# drv8886_breakout.net
KiCad netlist of a schematic drawn in Altium Designer
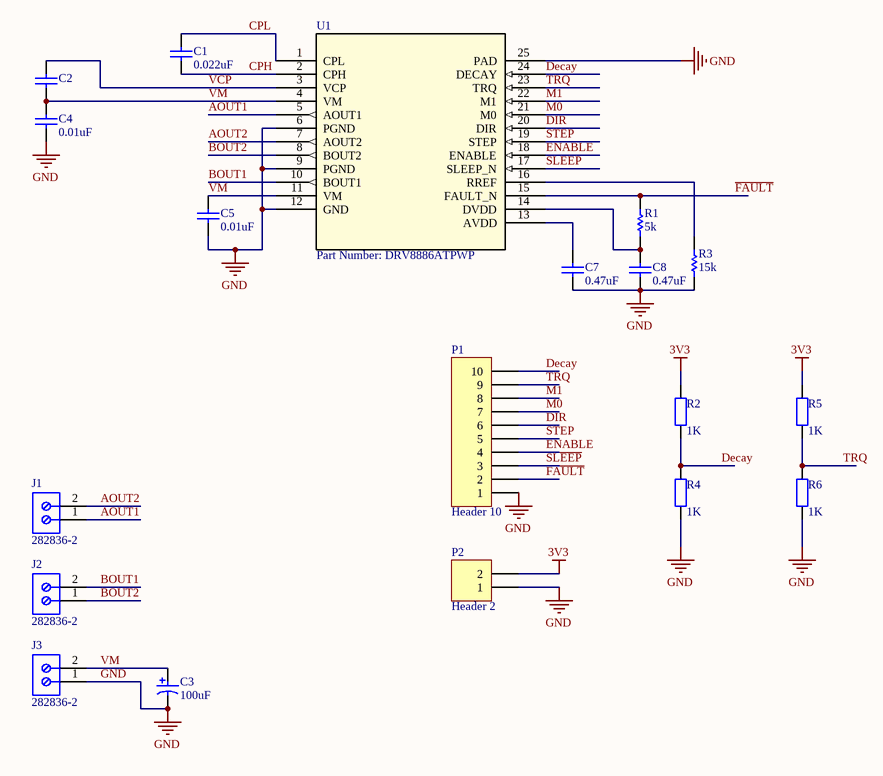
[diagram p0: drv8886_breakout.SchDoc]

(export (version "E")
  (design (tool "Eeschema 10.0.6"))
  (components
    (comp (ref "C1")
      (value "0.022uF")
      (footprint "CAPC1608X87X35ML15T15")
      (fields (field (name "PART NUMBER") "C0603C223K4RACTU") (field (name "MANUFACTURER") "Kemet"))
      (libsource (lib "Altium Content Vault") (part "CAP"))
    )
    (comp (ref "C2")
      (value "0.22uF")
      (footprint "TDK-C1608-2_A_M")
      (description "Cap Ceramic, 0.22 uF, +/- 10%, -55 to 125 degC, 2-Pin SMD (0603), RoHS, Tape and Reel")
      (fields (field (name "MANUFACTURER") "TDK") (field (name "TOLERANCE") "±10%"))
      (libsource (lib "Altium Content Vault") (part "CAP-NP-2"))
    )
    (comp (ref "C3")
      (value "100uF")
      (footprint "PNSC-FK-V-F_V")
      (fields (field (name "MANUFACTURER") "Panasonic"))
      (libsource (lib "Altium Content Vault") (part "CAP-P-2"))
    )
    (comp (ref "C4")
      (value "0.01uF")
      (footprint "CAPC1608X87X35LL15T15")
      (fields (field (name "MANUFACTURER") "Kemet") (field (name "PART NUMBER") "C0603X103K5RACTU"))
      (libsource (lib "Altium Content Vault") (part "CAP"))
    )
    (comp (ref "C5")
      (value "0.01uF")
      (footprint "CAPC1608X87X35LL15T15")
      (fields (field (name "MANUFACTURER") "Kemet") (field (name "PART NUMBER") "C0603X103K5RACTU"))
      (libsource (lib "Altium Content Vault") (part "CAP"))
    )
    (comp (ref "C7")
      (value "0.47uF")
      (footprint "CAPC1608X90X35ML15T15")
      (fields
        (field (name "PART NUMBER") "06033C474KAT2A")
        (field (name "MANUFACTURER") "AVX Interconnect / Elco")
      )
      (libsource (lib "Altium Content Vault") (part "CAP"))
    )
    (comp (ref "C8")
      (value "0.47uF")
      (footprint "CAPC1608X90X35ML15T15")
      (fields
        (field (name "PART NUMBER") "06033C474KAT2A")
        (field (name "MANUFACTURER") "AVX Interconnect / Elco")
      )
      (libsource (lib "Altium Content Vault") (part "CAP"))
    )
    (comp (ref "J1")
      (value "282836-2")
      (footprint "TECO-282836-2_V")
      (description "Female Header, Pitch 5 mm, 1 x 2 Position, Height 10 mm, Tail Length 3.5 mm, Rohs, Bulk")
      (fields (field (name "VOLTAGE") "300V") (field (name "MANUFACTURER") "TE Connectivity"))
      (libsource (lib "Altium Content Vault") (part "CN-1P-F-TB2"))
    )
    (comp (ref "J2")
      (value "282836-2")
      (footprint "TECO-282836-2_V")
      (description "Female Header, Pitch 5 mm, 1 x 2 Position, Height 10 mm, Tail Length 3.5 mm, Rohs, Bulk")
      (fields (field (name "VOLTAGE") "300V") (field (name "MANUFACTURER") "TE Connectivity"))
      (libsource (lib "Altium Content Vault") (part "CN-1P-F-TB2"))
    )
    (comp (ref "J3")
      (value "282836-2")
      (footprint "TECO-282836-2_V")
      (description "Female Header, Pitch 5 mm, 1 x 2 Position, Height 10 mm, Tail Length 3.5 mm, Rohs, Bulk")
      (fields (field (name "VOLTAGE") "300V") (field (name "MANUFACTURER") "TE Connectivity"))
      (libsource (lib "Altium Content Vault") (part "CN-1P-F-TB2"))
    )
    (comp (ref "P1")
      (value "Header 10")
      (footprint "HDR1X10")
      (description "Header, 10-Pin")
      (fields (field (name "PUBLISHER") "Altium Limited"))
      (libsource (lib "Miscellaneous Connectors") (part "Header 10"))
    )
    (comp (ref "P2")
      (value "Header 2")
      (footprint "HDR1X2")
      (description "Header, 2-Pin")
      (fields (field (name "PUBLISHER") "Altium Limited"))
      (libsource (lib "Miscellaneous Connectors") (part "Header 2"))
    )
    (comp (ref "R1")
      (value "5k")
      (footprint "RESC1608X55X25ML10T15")
      (description "Chip Resistor, 0 Ohm, +/- 5%, 0.1 W, -55 to 155 degC, 0603 (1608 Metric), RoHS, Tape and Reel")
      (fields (field (name "TOLERANCE") "5%") (field (name "MANUFACTURER") "Yageo"))
      (libsource (lib "Altium Content Vault") (part "RES-2"))
    )
    (comp (ref "R2")
      (value "1K")
      (footprint "AXIAL-0.4")
      (description "Resistor")
      (fields (field (name "Comment") "?") (field (name "PUBLISHER") "Altium Limited"))
      (libsource (lib "Miscellaneous Devices") (part "Res2"))
    )
    (comp (ref "R3")
      (value "15k")
      (footprint "RESC1608X55X25ML10T15")
      (description "Chip Resistor, 0 Ohm, +/- 5%, 0.1 W, -55 to 155 degC, 0603 (1608 Metric), RoHS, Tape and Reel")
      (fields (field (name "TOLERANCE") "5%") (field (name "MANUFACTURER") "Yageo"))
      (libsource (lib "Altium Content Vault") (part "RES-2"))
    )
    (comp (ref "R4")
      (value "1K")
      (footprint "AXIAL-0.4")
      (description "Resistor")
      (fields (field (name "Comment") "Res2") (field (name "PUBLISHER") "Altium Limited"))
      (libsource (lib "Miscellaneous Devices") (part "Res2"))
    )
    (comp (ref "R5")
      (value "1K")
      (footprint "AXIAL-0.4")
      (description "Resistor")
      (fields (field (name "Comment") "?") (field (name "PUBLISHER") "Altium Limited"))
      (libsource (lib "Miscellaneous Devices") (part "Res2"))
    )
    (comp (ref "R6")
      (value "1K")
      (footprint "AXIAL-0.4")
      (description "Resistor")
      (fields (field (name "Comment") "Res2") (field (name "PUBLISHER") "Altium Limited"))
      (libsource (lib "Miscellaneous Devices") (part "Res2"))
    )
    (comp (ref "U1")
      (value "Part Number: DRV8886ATPWP")
      (footprint "PWP0024B_N")
      (description "No Description Available")
      (fields
        (field (name "MANUFACTURER_PART_NUMBER") "DRV8886ATPWP")
        (field (name "COPYRIGHT") "Copyright (C) 2018 Accelerated Designs. All rights reserved")
      )
      (libsource (lib "2019-10-07_21-03-12") (part "DRV8886ATPWP"))
    )
  )
  (nets
    (net (code "1") (name "/AOUT1") (class "Default")
      (node (ref "J1") (pin "1") (pinfunction "1_1") (pintype "passive"))
      (node (ref "U1") (pin "5") (pinfunction "AOUT1_5") (pintype "output"))
    )
    (net (code "2") (name "/AOUT2") (class "Default")
      (node (ref "J1") (pin "2") (pinfunction "2_2") (pintype "passive"))
      (node (ref "U1") (pin "7") (pinfunction "AOUT2_7") (pintype "output"))
    )
    (net (code "3") (name "/BOUT1") (class "Default")
      (node (ref "J2") (pin "2") (pinfunction "2_2") (pintype "passive"))
      (node (ref "U1") (pin "10") (pinfunction "BOUT1_10") (pintype "output"))
    )
    (net (code "4") (name "/BOUT2") (class "Default")
      (node (ref "J2") (pin "1") (pinfunction "1_1") (pintype "passive"))
      (node (ref "U1") (pin "8") (pinfunction "BOUT2_8") (pintype "output"))
    )
    (net (code "5") (name "/CPH") (class "Default")
      (node (ref "C1") (pin "1") (pinfunction "1_1") (pintype "passive"))
      (node (ref "U1") (pin "2") (pinfunction "CPH_2") (pintype "passive"))
    )
    (net (code "6") (name "/CPL") (class "Default")
      (node (ref "C1") (pin "2") (pinfunction "2_2") (pintype "passive"))
      (node (ref "U1") (pin "1") (pinfunction "CPL_1") (pintype "passive"))
    )
    (net (code "7") (name "/DIR") (class "Default")
      (node (ref "P1") (pin "6") (pinfunction "6_6") (pintype "passive"))
      (node (ref "U1") (pin "20") (pinfunction "DIR_20") (pintype "input"))
    )
    (net (code "8") (name "/Decay") (class "Default")
      (node (ref "P1") (pin "10") (pinfunction "10_10") (pintype "passive"))
      (node (ref "R2") (pin "1") (pinfunction "1_1") (pintype "passive"))
      (node (ref "R4") (pin "2") (pinfunction "2_2") (pintype "passive"))
      (node (ref "U1") (pin "24") (pinfunction "DECAY_24") (pintype "input"))
    )
    (net (code "9") (name "/ENABLE") (class "Default")
      (node (ref "P1") (pin "4") (pinfunction "4_4") (pintype "passive"))
      (node (ref "U1") (pin "18") (pinfunction "ENABLE_18") (pintype "input"))
    )
    (net (code "10") (name "/FAULT") (class "Default")
      (node (ref "P1") (pin "2") (pinfunction "2_2") (pintype "passive"))
      (node (ref "R1") (pin "2") (pinfunction "2_2") (pintype "passive"))
      (node (ref "U1") (pin "15") (pinfunction "FAULT_N_15") (pintype "open_collector"))
    )
    (net (code "11") (name "/M0") (class "Default")
      (node (ref "P1") (pin "7") (pinfunction "7_7") (pintype "passive"))
      (node (ref "U1") (pin "21") (pinfunction "M0_21") (pintype "input"))
    )
    (net (code "12") (name "/M1") (class "Default")
      (node (ref "P1") (pin "8") (pinfunction "8_8") (pintype "passive"))
      (node (ref "U1") (pin "22") (pinfunction "M1_22") (pintype "input"))
    )
    (net (code "13") (name "/SLEEP") (class "Default")
      (node (ref "P1") (pin "3") (pinfunction "3_3") (pintype "passive"))
      (node (ref "U1") (pin "17") (pinfunction "SLEEP_N_17") (pintype "input"))
    )
    (net (code "14") (name "/STEP") (class "Default")
      (node (ref "P1") (pin "5") (pinfunction "5_5") (pintype "passive"))
      (node (ref "U1") (pin "19") (pinfunction "STEP_19") (pintype "input"))
    )
    (net (code "15") (name "/TRQ") (class "Default")
      (node (ref "P1") (pin "9") (pinfunction "9_9") (pintype "passive"))
      (node (ref "R5") (pin "1") (pinfunction "1_1") (pintype "passive"))
      (node (ref "R6") (pin "2") (pinfunction "2_2") (pintype "passive"))
      (node (ref "U1") (pin "23") (pinfunction "TRQ_23") (pintype "input"))
    )
    (net (code "16") (name "/VCP") (class "Default")
      (node (ref "C2") (pin "2") (pinfunction "2_2") (pintype "passive"))
      (node (ref "U1") (pin "3") (pinfunction "VCP_3") (pintype "passive"))
    )
    (net (code "17") (name "/VM") (class "Default")
      (node (ref "C2") (pin "1") (pinfunction "1_1") (pintype "passive"))
      (node (ref "C3") (pin "1") (pinfunction "1_1") (pintype "passive"))
      (node (ref "C4") (pin "1") (pinfunction "1_1") (pintype "passive"))
      (node (ref "C5") (pin "1") (pinfunction "1_1") (pintype "passive"))
      (node (ref "J3") (pin "2") (pinfunction "2_2") (pintype "passive"))
      (node (ref "U1") (pin "11") (pinfunction "VM_11") (pintype "power_in"))
      (node (ref "U1") (pin "4") (pinfunction "VM_4") (pintype "power_in"))
    )
    (net (code "18") (name "3V3") (class "Default")
      (node (ref "P2") (pin "2") (pinfunction "2_2") (pintype "passive"))
      (node (ref "R2") (pin "2") (pinfunction "2_2") (pintype "passive"))
      (node (ref "R5") (pin "2") (pinfunction "2_2") (pintype "passive"))
    )
    (net (code "19") (name "GND") (class "Default")
      (node (ref "C3") (pin "2") (pinfunction "2_2") (pintype "passive"))
      (node (ref "C4") (pin "2") (pinfunction "2_2") (pintype "passive"))
      (node (ref "C5") (pin "2") (pinfunction "2_2") (pintype "passive"))
      (node (ref "C7") (pin "1") (pinfunction "1_1") (pintype "passive"))
      (node (ref "C8") (pin "1") (pinfunction "1_1") (pintype "passive"))
      (node (ref "J3") (pin "1") (pinfunction "1_1") (pintype "passive"))
      (node (ref "P1") (pin "1") (pinfunction "1_1") (pintype "passive"))
      (node (ref "P2") (pin "1") (pinfunction "1_1") (pintype "passive"))
      (node (ref "R3") (pin "1") (pinfunction "1_1") (pintype "passive"))
      (node (ref "R4") (pin "1") (pinfunction "1_1") (pintype "passive"))
      (node (ref "R6") (pin "1") (pinfunction "1_1") (pintype "passive"))
      (node (ref "U1") (pin "12") (pinfunction "GND_12") (pintype "power_in"))
      (node (ref "U1") (pin "25") (pinfunction "PAD_25") (pintype "power_in"))
      (node (ref "U1") (pin "6") (pinfunction "PGND_6") (pintype "power_in"))
      (node (ref "U1") (pin "9") (pinfunction "PGND_9") (pintype "power_in"))
    )
    (net (code "20") (name "Net-(U1-AVDD)") (class "Default")
      (node (ref "C7") (pin "2") (pinfunction "2_2") (pintype "passive"))
      (node (ref "U1") (pin "13") (pinfunction "AVDD_13") (pintype "power_in"))
    )
    (net (code "21") (name "Net-(U1-DVDD)") (class "Default")
      (node (ref "C8") (pin "2") (pinfunction "2_2") (pintype "passive"))
      (node (ref "R1") (pin "1") (pinfunction "1_1") (pintype "passive"))
      (node (ref "U1") (pin "14") (pinfunction "DVDD_14") (pintype "power_in"))
    )
    (net (code "22") (name "Net-(U1-RREF)") (class "Default")
      (node (ref "R3") (pin "2") (pinfunction "2_2") (pintype "passive"))
      (node (ref "U1") (pin "16") (pinfunction "RREF_16") (pintype "passive"))
    )
  )
)
